# PCIE_x4_Edge_Connector_Interface.net
KiCad netlist of a schematic drawn in Altium Designer
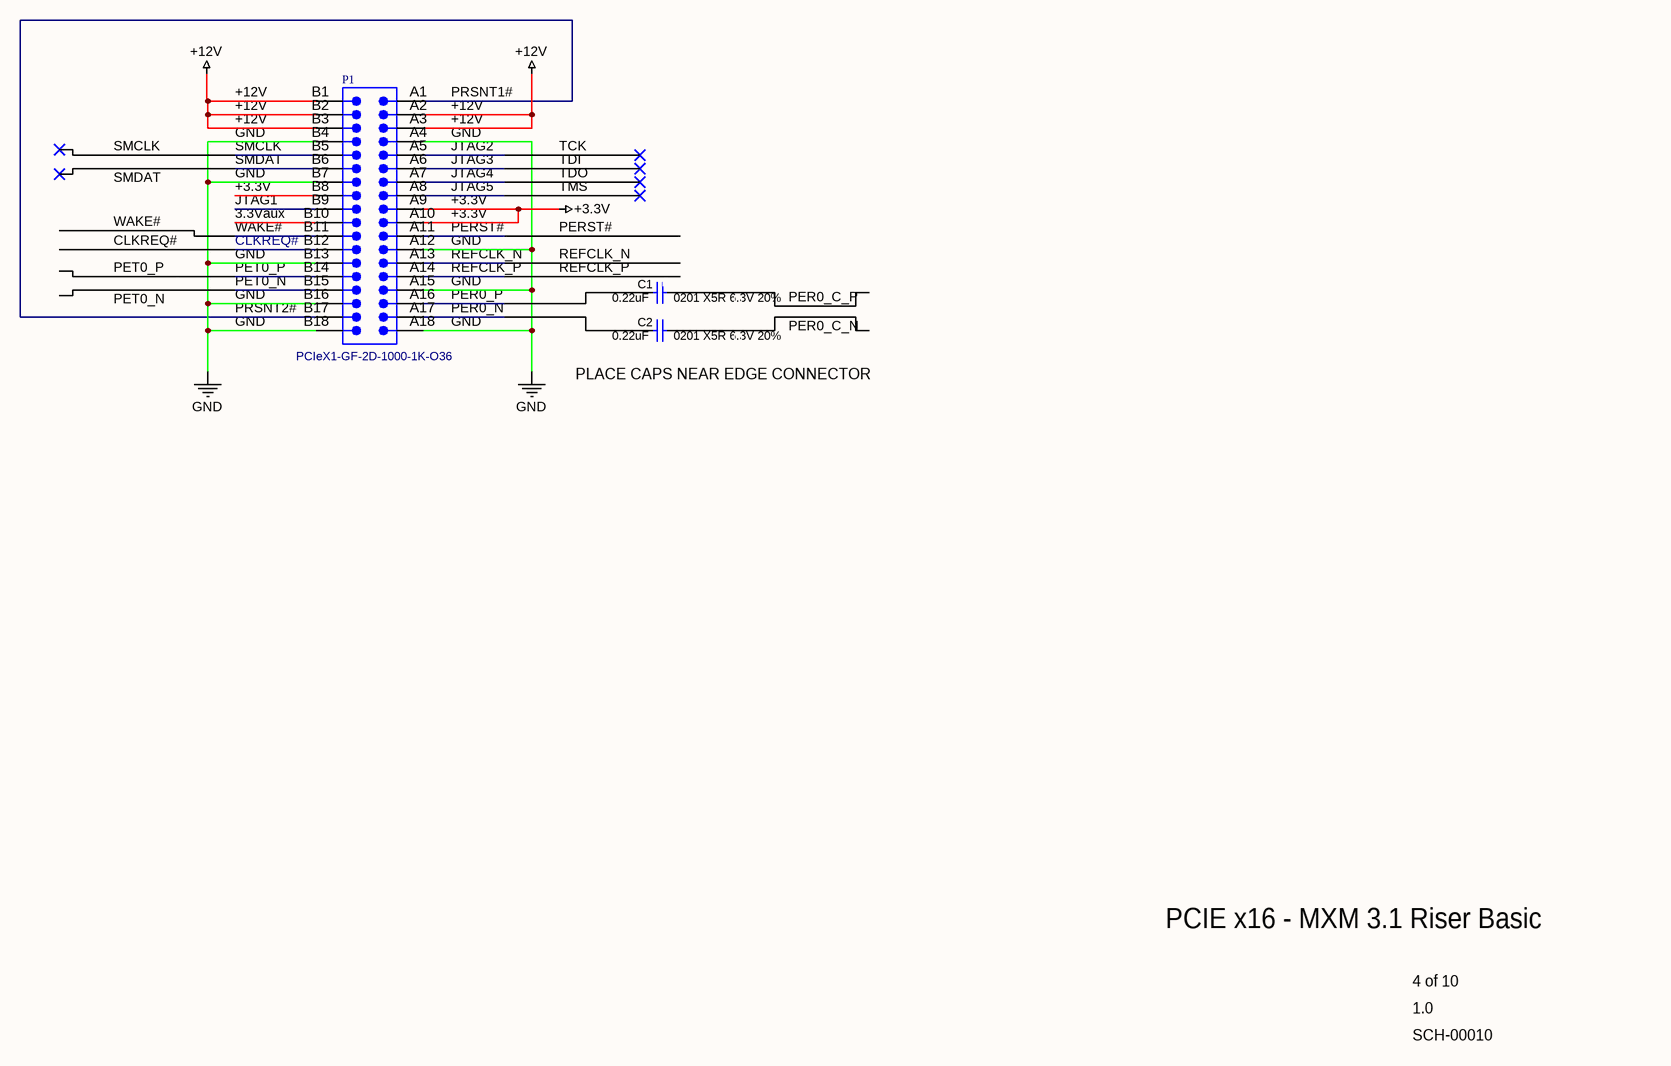
[diagram p0: PCIE x4 Edge Connector Interface.SchDoc]

(export (version "E")
  (design (tool "Eeschema 10.0.6"))
  (components
    (comp (ref "C1")
      (value "0.22uF       0201 X5R 6.3V 20%")
      (footprint "CAPC0603X33X15NL03T05")
      (fields (field (name "MANUFACTURER") "Samsung") (field (name "PART NUMBER") "CL03A224MQ3NNNC"))
      (libsource (lib "Altium Content Vault") (part "CAP"))
    )
    (comp (ref "C2")
      (value "0.22uF       0201 X5R 6.3V 20%")
      (footprint "CAPC0603X33X15NL03T05")
      (fields (field (name "MANUFACTURER") "Samsung") (field (name "PART NUMBER") "CL03A224MQ3NNNC"))
      (libsource (lib "Altium Content Vault") (part "CAP"))
    )
    (comp (ref "P1")
      (value "PCIeX1-GF-2D-1000-1K-O36")
      (footprint "PCIeX1-GF-2D-1000-1K-O36")
      (description "Golden finger, PCIeX1, Dual, Opposite, Pitch 1mm, 36-Position")
      (fields (field (name "PUBLISHER") "Altium"))
      (libsource (lib "Altium Shanghai") (part "PCIeX1-GF-2D-1000-1K-O36"))
    )
  )
  (nets
    (net (code "1") (name "+3.3V") (class "Default")
      (node (ref "P1") (pin "A10") (pinfunction "A10_A10") (pintype "passive"))
      (node (ref "P1") (pin "A9") (pinfunction "A9_A9") (pintype "passive"))
      (node (ref "P1") (pin "B8") (pinfunction "B8_B8") (pintype "passive"))
    )
    (net (code "2") (name "+12V") (class "Default")
      (node (ref "P1") (pin "A2") (pinfunction "A2_A2") (pintype "passive"))
      (node (ref "P1") (pin "A3") (pinfunction "A3_A3") (pintype "passive"))
      (node (ref "P1") (pin "B1") (pinfunction "B1_B1") (pintype "passive"))
      (node (ref "P1") (pin "B2") (pinfunction "B2_B2") (pintype "passive"))
      (node (ref "P1") (pin "B3") (pinfunction "B3_B3") (pintype "passive"))
    )
    (net (code "3") (name "/3.3Vaux") (class "Default")
      (node (ref "P1") (pin "B10") (pinfunction "B10_B10") (pintype "passive"))
    )
    (net (code "4") (name "/CLKREQ#") (class "Default")
      (node (ref "P1") (pin "B12") (pinfunction "B12_B12") (pintype "passive"))
    )
    (net (code "5") (name "/JTAG1") (class "Default")
      (node (ref "P1") (pin "B9") (pinfunction "B9_B9") (pintype "passive"))
    )
    (net (code "6") (name "/JTAG2") (class "Default")
      (node (ref "P1") (pin "A5") (pinfunction "A5_A5") (pintype "passive+no_connect"))
    )
    (net (code "7") (name "/JTAG3") (class "Default")
      (node (ref "P1") (pin "A6") (pinfunction "A6_A6") (pintype "passive+no_connect"))
    )
    (net (code "8") (name "/JTAG4") (class "Default")
      (node (ref "P1") (pin "A7") (pinfunction "A7_A7") (pintype "passive+no_connect"))
    )
    (net (code "9") (name "/JTAG5") (class "Default")
      (node (ref "P1") (pin "A8") (pinfunction "A8_A8") (pintype "passive+no_connect"))
    )
    (net (code "10") (name "/PER0_C_N") (class "Default")
      (node (ref "C2") (pin "2") (pinfunction "2_2") (pintype "passive"))
    )
    (net (code "11") (name "/PER0_C_P") (class "Default")
      (node (ref "C1") (pin "2") (pinfunction "2_2") (pintype "passive"))
    )
    (net (code "12") (name "/PER0_N") (class "Default")
      (node (ref "C2") (pin "1") (pinfunction "1_1") (pintype "passive"))
      (node (ref "P1") (pin "A17") (pinfunction "A17_A17") (pintype "passive"))
    )
    (net (code "13") (name "/PER0_P") (class "Default")
      (node (ref "C1") (pin "1") (pinfunction "1_1") (pintype "passive"))
      (node (ref "P1") (pin "A16") (pinfunction "A16_A16") (pintype "passive"))
    )
    (net (code "14") (name "/PERST#") (class "Default")
      (node (ref "P1") (pin "A11") (pinfunction "A11_A11") (pintype "passive"))
    )
    (net (code "15") (name "/PET0_N") (class "Default")
      (node (ref "P1") (pin "B15") (pinfunction "B15_B15") (pintype "passive"))
    )
    (net (code "16") (name "/PET0_P") (class "Default")
      (node (ref "P1") (pin "B14") (pinfunction "B14_B14") (pintype "passive"))
    )
    (net (code "17") (name "/PRSNT1#") (class "Default")
      (node (ref "P1") (pin "A1") (pinfunction "A1_A1") (pintype "passive"))
      (node (ref "P1") (pin "B17") (pinfunction "B17_B17") (pintype "passive"))
    )
    (net (code "18") (name "/REFCLK_N") (class "Default")
      (node (ref "P1") (pin "A13") (pinfunction "A13_A13") (pintype "passive"))
    )
    (net (code "19") (name "/REFCLK_P") (class "Default")
      (node (ref "P1") (pin "A14") (pinfunction "A14_A14") (pintype "passive"))
    )
    (net (code "20") (name "/SMCLK") (class "Default")
      (node (ref "P1") (pin "B5") (pinfunction "B5_B5") (pintype "passive+no_connect"))
    )
    (net (code "21") (name "/SMDAT") (class "Default")
      (node (ref "P1") (pin "B6") (pinfunction "B6_B6") (pintype "passive+no_connect"))
    )
    (net (code "22") (name "/WAKE#") (class "Default")
      (node (ref "P1") (pin "B11") (pinfunction "B11_B11") (pintype "passive"))
    )
    (net (code "23") (name "GND") (class "Default")
      (node (ref "P1") (pin "A12") (pinfunction "A12_A12") (pintype "passive"))
      (node (ref "P1") (pin "A15") (pinfunction "A15_A15") (pintype "passive"))
      (node (ref "P1") (pin "A18") (pinfunction "A18_A18") (pintype "passive"))
      (node (ref "P1") (pin "A4") (pinfunction "A4_A4") (pintype "passive"))
      (node (ref "P1") (pin "B13") (pinfunction "B13_B13") (pintype "passive"))
      (node (ref "P1") (pin "B16") (pinfunction "B16_B16") (pintype "passive"))
      (node (ref "P1") (pin "B18") (pinfunction "B18_B18") (pintype "passive"))
      (node (ref "P1") (pin "B4") (pinfunction "B4_B4") (pintype "passive"))
      (node (ref "P1") (pin "B7") (pinfunction "B7_B7") (pintype "passive"))
    )
  )
)
